# ProDoc_P1_2024-07-02.net
KiCad netlist of a schematic drawn in EasyEDA Pro
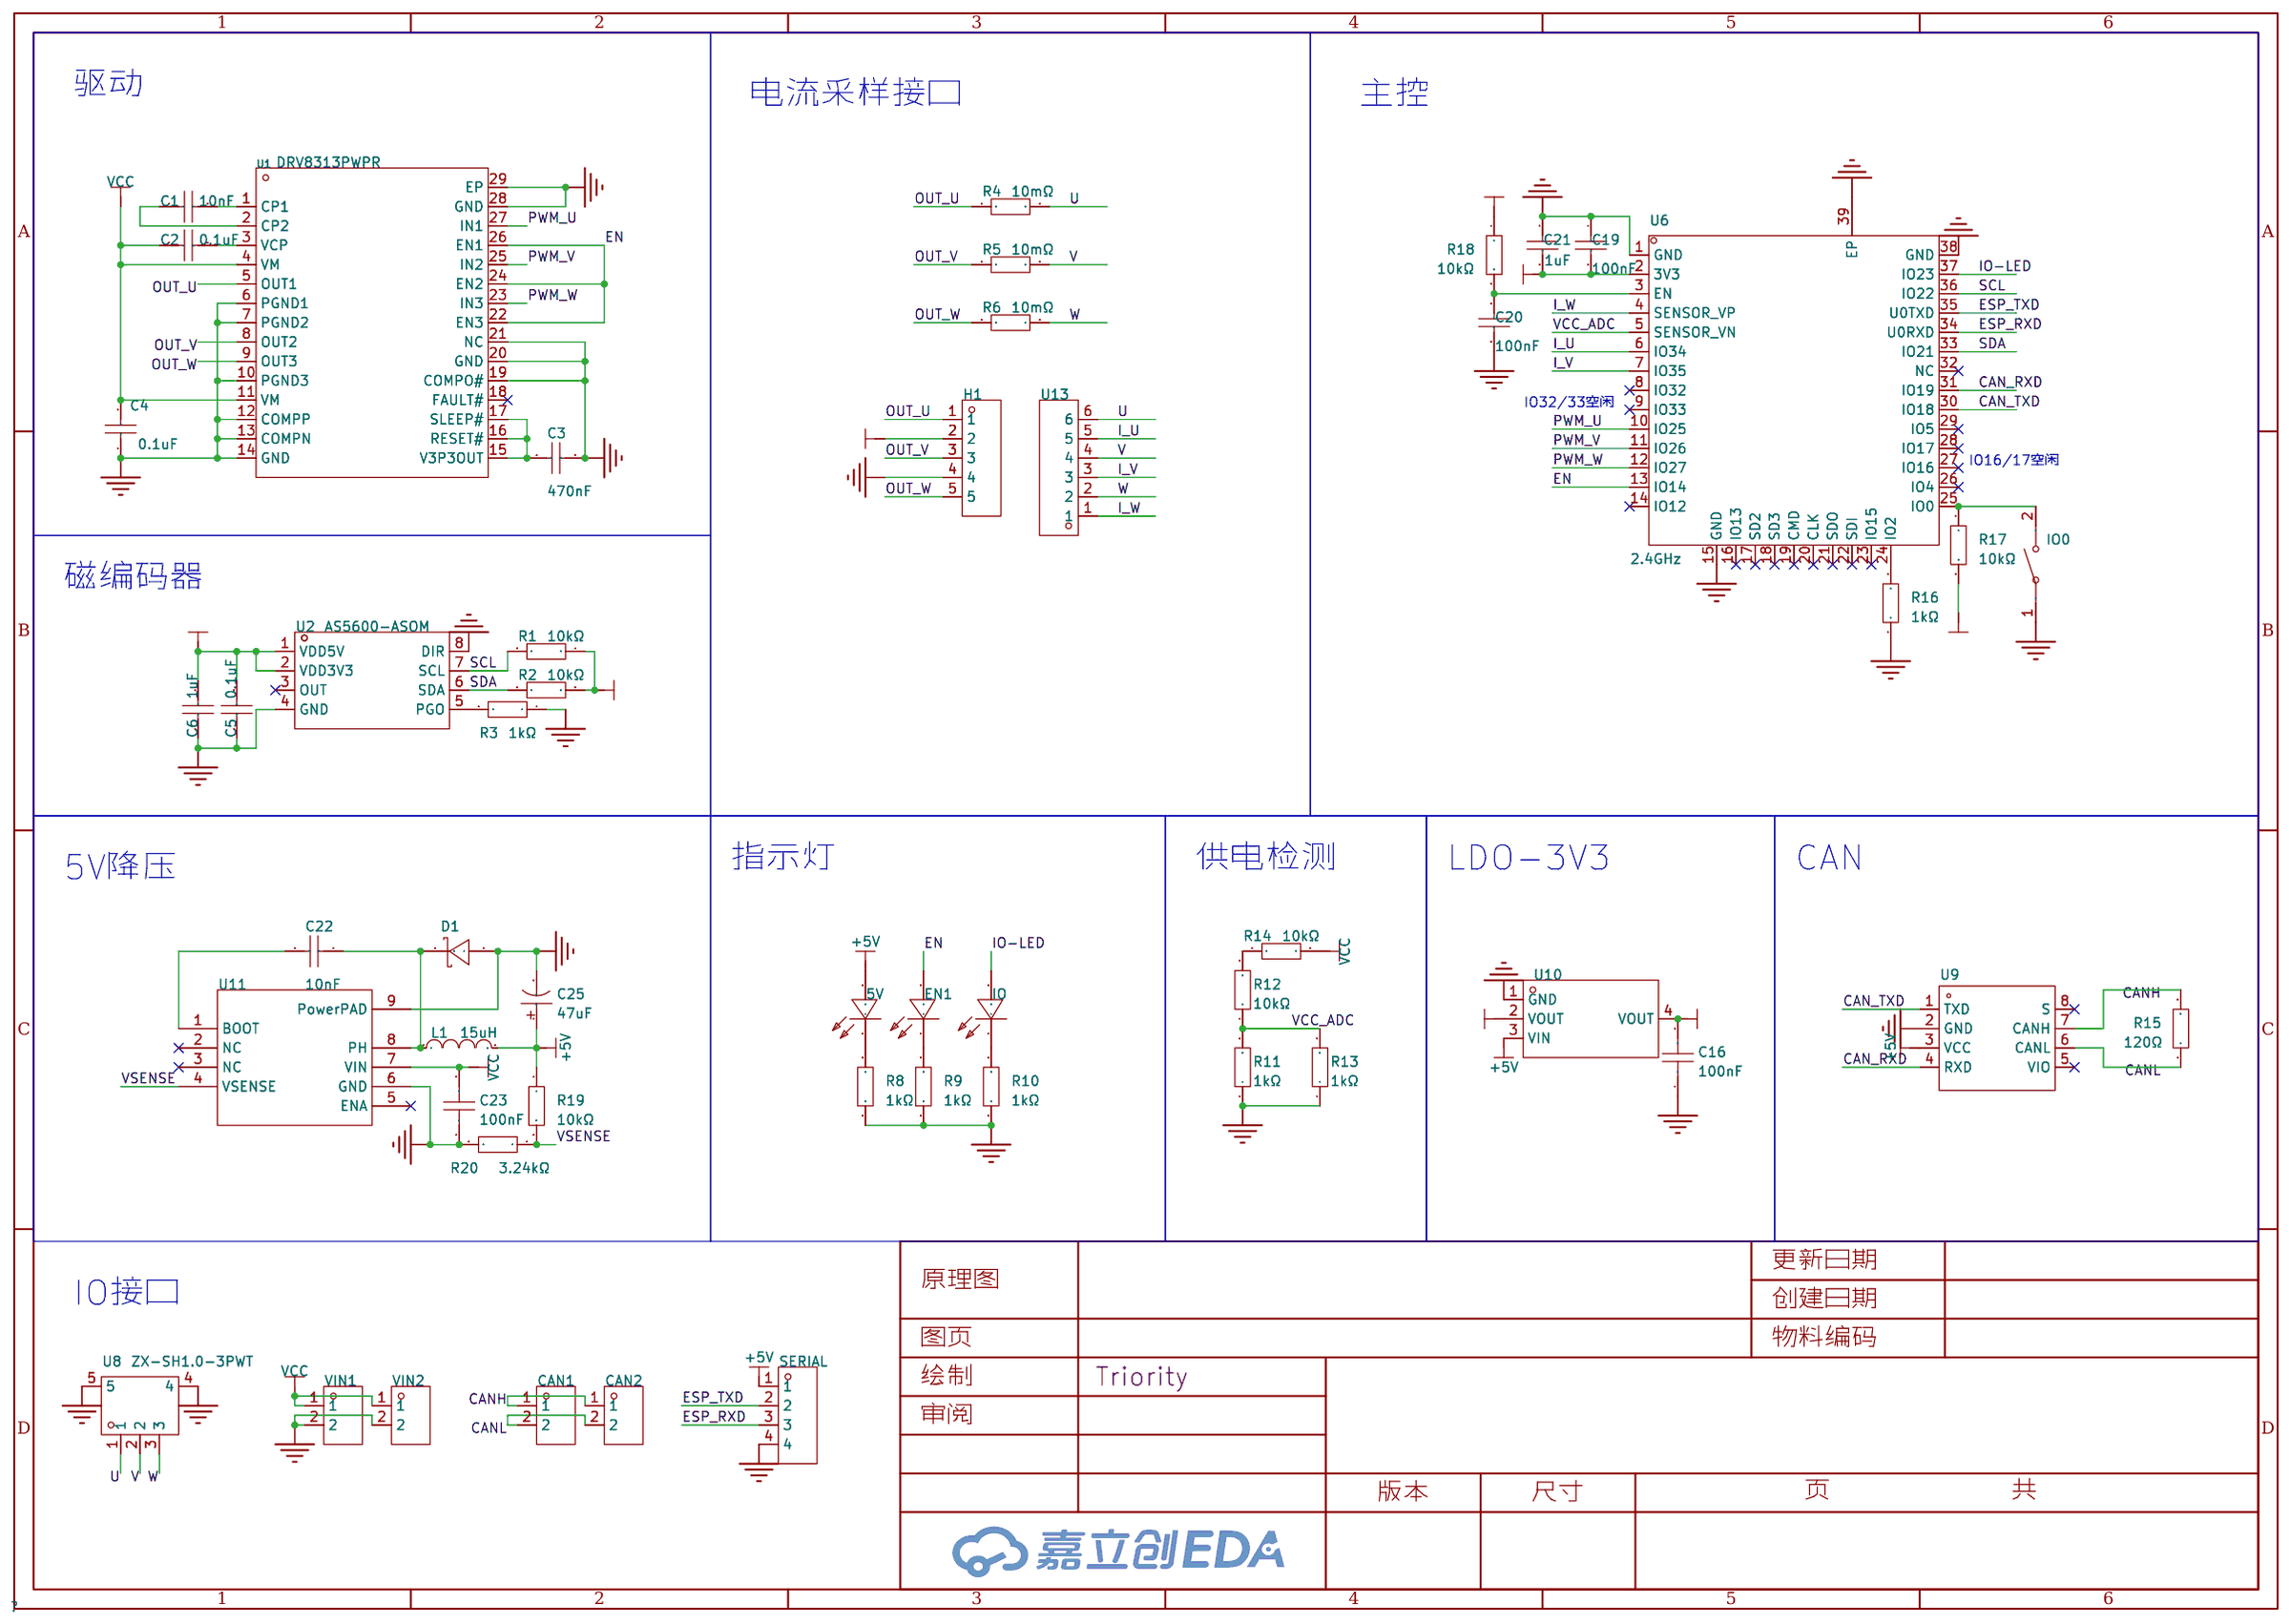
[diagram p0: schematic sheet]

(export (version "E")
  (design (tool "Eeschema 10.0.6"))
  (components
    (comp (ref "5V")
      (value "KT-0603R")
      (footprint "easyedapro:LED0603-RD")
      (description "发光颜色:红色;功率:-;正向电流:-;主波长:-;二极管配置:-;透镜颜色:-;色温:-;发光角度:-;载带方式:-;工作温度:-40°C~+85°C;")
      (fields (field (name "Manufacturer") "KENTO"))
      (libsource (lib "easyedapro") (part "KT-0603R"))
    )
    (comp (ref "C1")
      (value "10nF")
      (footprint "easyedapro:C0603")
      (description "容值:10nF;精度:±10%;额定电压:50V;材质(温度系数):X7R;")
      (fields
        (field (name "Manufacturer Part") "CC0603KRX7R9BB103")
        (field (name "Manufacturer") "YAGEO(国巨)")
      )
      (libsource (lib "easyedapro") (part "CC0603KRX7R9BB103"))
    )
    (comp (ref "C2")
      (value "0.1uF")
      (footprint "easyedapro:C0603")
      (description "容值:100nF;精度:±10%;额定电压:50V;材质(温度系数):X7R;")
      (fields (field (name "Manufacturer Part") "0603B104K500NT") (field (name "Manufacturer") "FH(风华)"))
      (libsource (lib "easyedapro") (part "0603B104K500NT"))
    )
    (comp (ref "C3")
      (value "470nF")
      (footprint "easyedapro:C0603")
      (description "容值:470nF;精度:±10%;额定电压:25V;材质(温度系数):X7R;")
      (fields
        (field (name "Manufacturer Part") "CL10B474KA8NNNC")
        (field (name "Manufacturer") "SAMSUNG(三星)")
      )
      (libsource (lib "easyedapro") (part "CL10B474KA8NNNC"))
    )
    (comp (ref "C4")
      (value "0.1uF")
      (footprint "easyedapro:C0603")
      (description "容值:100nF;精度:±10%;额定电压:50V;材质(温度系数):X7R;")
      (fields (field (name "Manufacturer Part") "0603B104K500NT") (field (name "Manufacturer") "FH(风华)"))
      (libsource (lib "easyedapro") (part "0603B104K500NT"))
    )
    (comp (ref "C5")
      (value "0.1uF")
      (footprint "easyedapro:C0603")
      (description "容值:100nF;精度:±10%;额定电压:50V;材质(温度系数):X7R;")
      (fields (field (name "Manufacturer Part") "0603B104K500NT") (field (name "Manufacturer") "FH(风华)"))
      (libsource (lib "easyedapro") (part "0603B104K500NT"))
    )
    (comp (ref "C6")
      (value "1uF")
      (footprint "easyedapro:C0603")
      (description "容值:1uF;精度:±10%;额定电压:50V;材质(温度系数):X5R;")
      (fields
        (field (name "Manufacturer Part") "CL10A105KB8NNNC")
        (field (name "Manufacturer") "SAMSUNG(三星)")
      )
      (libsource (lib "easyedapro") (part "CL10A105KB8NNNC"))
    )
    (comp (ref "C16")
      (value "100nF")
      (footprint "easyedapro:C0603")
      (description "容值:100nF;精度:±10%;额定电压:50V;材质(温度系数):X7R;")
      (fields
        (field (name "Manufacturer Part") "CC0603KRX7R9BB104")
        (field (name "Manufacturer") "YAGEO(国巨)")
      )
      (libsource (lib "easyedapro") (part "CC0603KRX7R9BB104"))
    )
    (comp (ref "C19")
      (value "100nF")
      (footprint "easyedapro:C0603")
      (description "容值:100nF;精度:±10%;额定电压:50V;材质(温度系数):X7R;")
      (fields (field (name "Manufacturer Part") "0603B104K500NT") (field (name "Manufacturer") "FH(风华)"))
      (libsource (lib "easyedapro") (part "0603B104K500NT"))
    )
    (comp (ref "C20")
      (value "100nF")
      (footprint "easyedapro:C0603")
      (description "容值:100nF;精度:±10%;额定电压:50V;材质(温度系数):X7R;")
      (fields (field (name "Manufacturer Part") "0603B104K500NT") (field (name "Manufacturer") "FH(风华)"))
      (libsource (lib "easyedapro") (part "0603B104K500NT"))
    )
    (comp (ref "C21")
      (value "1uF")
      (footprint "easyedapro:C0603")
      (description "容值:1uF;精度:±10%;额定电压:50V;材质(温度系数):X5R;")
      (fields
        (field (name "Manufacturer Part") "CL10A105KB8NNNC")
        (field (name "Manufacturer") "SAMSUNG(三星)")
      )
      (libsource (lib "easyedapro") (part "CL10A105KB8NNNC"))
    )
    (comp (ref "C22")
      (value "10nF")
      (footprint "easyedapro:C0603")
      (description "容值:10nF;精度:±10%;额定电压:50V;材质(温度系数):X7R;")
      (fields (field (name "Manufacturer Part") "0603B103K500NT") (field (name "Manufacturer") "FH(风华)"))
      (libsource (lib "easyedapro") (part "0603B103K500NT"))
    )
    (comp (ref "C23")
      (value "100nF")
      (footprint "easyedapro:C0603")
      (description "容值:100nF;精度:±10%;额定电压:50V;材质(温度系数):X7R;")
      (fields
        (field (name "Manufacturer Part") "CC0603KRX7R9BB104")
        (field (name "Manufacturer") "YAGEO(国巨)")
      )
      (libsource (lib "easyedapro") (part "CC0603KRX7R9BB104"))
    )
    (comp (ref "C25")
      (value "47uF")
      (footprint "easyedapro:CAP-SMD_BD4.0-L4.3-W4.3-LS5.3-FD")
      (description "容值:47uF;精度:±20%;额定电压:10V;纹波电流:31mA@120Hz;等效串联电阻:-;")
      (fields (field (name "Manufacturer Part") "RVT1A470M0405") (field (name "Manufacturer") "ROQANG(容强)"))
      (libsource (lib "easyedapro") (part "RVT1A470M0405"))
    )
    (comp (ref "CAN1")
      (value "ZX-XH2.54-2PWZ")
      (footprint "easyedapro:CONN-TH_2P-P2.50_ZX-XH2.54-2PWZ")
      (fields (field (name "Manufacturer") "Megastar(兆星)"))
      (libsource (lib "easyedapro") (part "ZX-XH2.54-2PWZ"))
    )
    (comp (ref "CAN2")
      (value "ZX-XH2.54-2PWZ")
      (footprint "easyedapro:CONN-TH_2P-P2.50_ZX-XH2.54-2PWZ")
      (fields (field (name "Manufacturer") "Megastar(兆星)"))
      (libsource (lib "easyedapro") (part "ZX-XH2.54-2PWZ"))
    )
    (comp (ref "D1")
      (value "B340A")
      (footprint "easyedapro:SMA_L4.3-W2.6-LS5.1-RD")
      (description "二极管配置:独立式;正向压降(Vf):550mV@3A;直流反向耐压(Vr):40V;整流电流:3A;")
      (fields (field (name "Manufacturer") "MDD(辰达半导体)"))
      (libsource (lib "easyedapro") (part "B340A"))
    )
    (comp (ref "EN1")
      (value "KT-0603R")
      (footprint "easyedapro:LED0603-RD")
      (description "发光颜色:红色;功率:-;正向电流:-;主波长:-;二极管配置:-;透镜颜色:-;色温:-;发光角度:-;载带方式:-;工作温度:-40°C~+85°C;")
      (fields (field (name "Manufacturer") "KENTO"))
      (libsource (lib "easyedapro") (part "KT-0603R"))
    )
    (comp (ref "H1")
      (value "PZ254V-11-05P")
      (footprint "easyedapro:HDR-TH_5P-P2.54-V-M")
      (fields (field (name "Manufacturer") "XFCN(兴飞)"))
      (libsource (lib "easyedapro") (part "PZ254V-11-05P"))
    )
    (comp (ref "IO")
      (value "KT-0603R")
      (footprint "easyedapro:LED0603-RD")
      (description "发光颜色:红色;功率:-;正向电流:-;主波长:-;二极管配置:-;透镜颜色:-;色温:-;发光角度:-;载带方式:-;工作温度:-40°C~+85°C;")
      (fields (field (name "Manufacturer") "KENTO"))
      (libsource (lib "easyedapro") (part "KT-0603R"))
    )
    (comp (ref "IO0")
      (value "K2-1107ST-A4DW-06")
      (footprint "easyedapro:KEY-SMD_L6.2-W3.6-LS8.0")
      (fields (field (name "Manufacturer") "韩国韩荣"))
      (libsource (lib "easyedapro") (part "K2-1107ST-A4SW-06"))
    )
    (comp (ref "L1")
      (value "15uH")
      (footprint "easyedapro:IND-SMD_L7.3-W6.8")
      (description "电感值:15uH;精度:±20%;额定电流:3A;饱和电流(Isat):4A;类型:-;")
      (fields
        (field (name "Manufacturer Part") "MWSA0603S-150MT")
        (field (name "Manufacturer") "Sunlord(顺络)")
      )
      (libsource (lib "easyedapro") (part "MWSA0603S-150MT"))
    )
    (comp (ref "R1")
      (value "10kΩ")
      (footprint "easyedapro:R0603")
      (description "电阻类型:厚膜电阻;阻值:10kΩ;精度:±1%;功率:100mW;最大工作电压:75V;温度系数:±100ppm/°C;")
      (fields (field (name "Manufacturer Part") "RC0603FR-0710KL") (field (name "Manufacturer") "YAGEO(国巨)"))
      (libsource (lib "easyedapro") (part "RC0603FR-0710KL"))
    )
    (comp (ref "R2")
      (value "10kΩ")
      (footprint "easyedapro:R0603")
      (description "电阻类型:厚膜电阻;阻值:10kΩ;精度:±1%;功率:100mW;最大工作电压:75V;温度系数:±100ppm/°C;")
      (fields (field (name "Manufacturer Part") "RC0603FR-0710KL") (field (name "Manufacturer") "YAGEO(国巨)"))
      (libsource (lib "easyedapro") (part "RC0603FR-0710KL"))
    )
    (comp (ref "R3")
      (value "1kΩ")
      (footprint "easyedapro:R0603")
      (description "电阻类型:厚膜电阻;阻值:1kΩ;精度:±1%;功率:100mW;最大工作电压:75V;温度系数:±100ppm/°C;")
      (fields (field (name "Manufacturer Part") "RC0603FR-071KL") (field (name "Manufacturer") "YAGEO(国巨)"))
      (libsource (lib "easyedapro") (part "RC0603FR-071KL"))
    )
    (comp (ref "R4")
      (value "10mΩ")
      (footprint "easyedapro:R1206")
      (description "阻值:10mΩ;精度:±1%;功率:1W;温度系数:±100ppm/°C;")
      (fields (field (name "Manufacturer Part") "RLM12FTCMR010") (field (name "Manufacturer") "大毅科技"))
      (libsource (lib "easyedapro") (part "RLM12FTCMR010"))
    )
    (comp (ref "R5")
      (value "10mΩ")
      (footprint "easyedapro:R1206")
      (description "阻值:10mΩ;精度:±1%;功率:1W;温度系数:±100ppm/°C;")
      (fields (field (name "Manufacturer Part") "RLM12FTCMR010") (field (name "Manufacturer") "大毅科技"))
      (libsource (lib "easyedapro") (part "RLM12FTCMR010"))
    )
    (comp (ref "R6")
      (value "10mΩ")
      (footprint "easyedapro:R1206")
      (description "阻值:10mΩ;精度:±1%;功率:1W;温度系数:±100ppm/°C;")
      (fields (field (name "Manufacturer Part") "RLM12FTCMR010") (field (name "Manufacturer") "大毅科技"))
      (libsource (lib "easyedapro") (part "RLM12FTCMR010"))
    )
    (comp (ref "R8")
      (value "1kΩ")
      (footprint "easyedapro:R0603")
      (description "电阻类型:厚膜电阻;阻值:1kΩ;精度:±1%;功率:100mW;最大工作电压:75V;温度系数:±100ppm/°C;")
      (fields
        (field (name "Manufacturer Part") "0603WAF1001T5E")
        (field (name "Manufacturer") "UNI-ROYAL(厚声)")
      )
      (libsource (lib "easyedapro") (part "0603WAF1001T5E"))
    )
    (comp (ref "R9")
      (value "1kΩ")
      (footprint "easyedapro:R0603")
      (description "电阻类型:厚膜电阻;阻值:1kΩ;精度:±1%;功率:100mW;最大工作电压:75V;温度系数:±100ppm/°C;")
      (fields
        (field (name "Manufacturer Part") "0603WAF1001T5E")
        (field (name "Manufacturer") "UNI-ROYAL(厚声)")
      )
      (libsource (lib "easyedapro") (part "0603WAF1001T5E"))
    )
    (comp (ref "R10")
      (value "1kΩ")
      (footprint "easyedapro:R0603")
      (description "电阻类型:厚膜电阻;阻值:1kΩ;精度:±1%;功率:100mW;最大工作电压:75V;温度系数:±100ppm/°C;")
      (fields
        (field (name "Manufacturer Part") "0603WAF1001T5E")
        (field (name "Manufacturer") "UNI-ROYAL(厚声)")
      )
      (libsource (lib "easyedapro") (part "0603WAF1001T5E"))
    )
    (comp (ref "R11")
      (value "1kΩ")
      (footprint "easyedapro:R0603")
      (description "电阻类型:厚膜电阻;阻值:1kΩ;精度:±1%;功率:100mW;最大工作电压:75V;温度系数:±100ppm/°C;")
      (fields
        (field (name "Manufacturer Part") "0603WAF1001T5E")
        (field (name "Manufacturer") "UNI-ROYAL(厚声)")
      )
      (libsource (lib "easyedapro") (part "0603WAF1001T5E"))
    )
    (comp (ref "R12")
      (value "10kΩ")
      (footprint "easyedapro:R0603")
      (description "电阻类型:厚膜电阻;阻值:10kΩ;精度:±1%;功率:100mW;最大工作电压:75V;温度系数:±100ppm/°C;")
      (fields (field (name "Manufacturer Part") "RC0603FR-0710KL") (field (name "Manufacturer") "YAGEO(国巨)"))
      (libsource (lib "easyedapro") (part "RC0603FR-0710KL"))
    )
    (comp (ref "R13")
      (value "1kΩ")
      (footprint "easyedapro:R0603")
      (description "电阻类型:厚膜电阻;阻值:1kΩ;精度:±1%;功率:100mW;最大工作电压:75V;温度系数:±100ppm/°C;")
      (fields
        (field (name "Manufacturer Part") "0603WAF1001T5E")
        (field (name "Manufacturer") "UNI-ROYAL(厚声)")
      )
      (libsource (lib "easyedapro") (part "0603WAF1001T5E"))
    )
    (comp (ref "R14")
      (value "10kΩ")
      (footprint "easyedapro:R0603")
      (description "电阻类型:厚膜电阻;阻值:10kΩ;精度:±1%;功率:100mW;最大工作电压:75V;温度系数:±100ppm/°C;")
      (fields (field (name "Manufacturer Part") "RC0603FR-0710KL") (field (name "Manufacturer") "YAGEO(国巨)"))
      (libsource (lib "easyedapro") (part "RC0603FR-0710KL"))
    )
    (comp (ref "R15")
      (value "120Ω")
      (footprint "easyedapro:R0603")
      (description "电阻类型:厚膜电阻;阻值:120Ω;精度:±1%;功率:100mW;最大工作电压:75V;温度系数:±100ppm/°C;")
      (fields
        (field (name "Manufacturer Part") "0603WAF1200T5E")
        (field (name "Manufacturer") "UNI-ROYAL(厚声)")
      )
      (libsource (lib "easyedapro") (part "0603WAF1200T5E"))
    )
    (comp (ref "R16")
      (value "1kΩ")
      (footprint "easyedapro:R0603")
      (description "电阻类型:厚膜电阻;阻值:1kΩ;精度:±1%;功率:100mW;最大工作电压:75V;温度系数:±100ppm/°C;")
      (fields
        (field (name "Manufacturer Part") "0603WAF1001T5E")
        (field (name "Manufacturer") "UNI-ROYAL(厚声)")
      )
      (libsource (lib "easyedapro") (part "0603WAF1001T5E"))
    )
    (comp (ref "R17")
      (value "10kΩ")
      (footprint "easyedapro:R0603")
      (description "电阻类型:厚膜电阻;阻值:10kΩ;精度:±1%;功率:100mW;最大工作电压:75V;温度系数:±100ppm/°C;")
      (fields (field (name "Manufacturer Part") "RC0603FR-0710KL") (field (name "Manufacturer") "YAGEO(国巨)"))
      (libsource (lib "easyedapro") (part "RC0603FR-0710KL"))
    )
    (comp (ref "R18")
      (value "10kΩ")
      (footprint "easyedapro:R0603")
      (description "电阻类型:厚膜电阻;阻值:10kΩ;精度:±1%;功率:100mW;最大工作电压:75V;温度系数:±100ppm/°C;")
      (fields (field (name "Manufacturer Part") "RC0603FR-0710KL") (field (name "Manufacturer") "YAGEO(国巨)"))
      (libsource (lib "easyedapro") (part "RC0603FR-0710KL"))
    )
    (comp (ref "R19")
      (value "10kΩ")
      (footprint "easyedapro:R0603")
      (description "电阻类型:厚膜电阻;阻值:10kΩ;精度:±1%;功率:100mW;最大工作电压:75V;温度系数:±100ppm/°C;")
      (fields (field (name "Manufacturer Part") "RC0603FR-0710KL") (field (name "Manufacturer") "YAGEO(国巨)"))
      (libsource (lib "easyedapro") (part "RC0603FR-0710KL"))
    )
    (comp (ref "R20")
      (value "3.24kΩ")
      (footprint "easyedapro:R0603")
      (description "电阻类型:厚膜电阻;阻值:3.24kΩ;精度:±1%;功率:100mW;最大工作电压:75V;温度系数:±100ppm/°C;")
      (fields
        (field (name "Manufacturer Part") "0603WAF3241T5E")
        (field (name "Manufacturer") "UNI-ROYAL(厚声)")
      )
      (libsource (lib "easyedapro") (part "0603WAF3241T5E"))
    )
    (comp (ref "SERIAL")
      (value "WAFER-XH2.54-4PWZ")
      (footprint "easyedapro:CONN-TH_4P-P2.50_WAFER-XH2.54-4PWZ")
      (description "插针结构:1x4P;间距:2.54mm;安装方式:弯插;总PIN数:4P;排数:1;每排PIN数:4;额定电流:2A;工作温度范围:-25°C~+85°C;")
      (fields (field (name "Manufacturer") "XUNPU(讯普)"))
      (libsource (lib "easyedapro") (part "WAFER-XH2.54-4PWZ"))
    )
    (comp (ref "U1")
      (value "DRV8313PWPR")
      (footprint "easyedapro:HTSSOP-28_L9.8-W4.5-P0.65-LS6.6-BL-EP")
      (description "驱动电机类型:无刷直流BLDC;电源电压:8V~60V;输出电流:-;接口:并行;")
      (fields (field (name "Manufacturer") "TI(德州仪器)"))
      (libsource (lib "easyedapro") (part "DRV8313PWPR"))
    )
    (comp (ref "U2")
      (value "AS5600-ASOM")
      (footprint "easyedapro:SOIC-8_L5.0-W4.0-P1.27-LS6.0-BL")
      (description "旋转角度范围:0°~360°;")
      (fields (field (name "Manufacturer") "ams(艾迈斯半导体)"))
      (libsource (lib "easyedapro") (part "AS5600-ASOM"))
    )
    (comp (ref "U6")
      (value "2.4GHz")
      (footprint "easyedapro:WIRELM-SMD_ESP32-S")
      (description "核心处理器:ESP32芯片;频率:2.4GHz;天线形式:IPEX接口;发射功率:17dBm;接收灵敏度:-90dBm;")
      (fields (field (name "Manufacturer Part") "ESP32-S") (field (name "Manufacturer") "Ai-Thinker(安信可)"))
      (libsource (lib "easyedapro") (part "ESP32-S"))
    )
    (comp (ref "U8")
      (value "ZX-SH1.0-3PWT")
      (footprint "easyedapro:CONN-SMD_3P-P1.00_MEGASTAR_ZX-SH1.0-3PWT")
      (fields (field (name "Manufacturer") "Megastar(兆星)"))
      (libsource (lib "easyedapro") (part "ZX-SH1.0-3PWT"))
    )
    (comp (ref "U9")
      (value "TJA1051T/3/1J")
      (footprint "easyedapro:SOIC-8_L4.9-W3.9-P1.27-LS6.0-BL")
      (description "类型:收发器;数据速率:5Mbps;")
      (fields (field (name "Manufacturer") "NXP(恩智浦)"))
      (libsource (lib "easyedapro") (part "TJA1051T/3/1J"))
    )
    (comp (ref "U10")
      (value "AMS1117-3.3")
      (footprint "easyedapro:SOT-223-3_L6.5-W3.4-P2.30-LS7.0-BR")
      (description "输出类型:固定;最大输入电压:-;输出电压:3.3V;最大输出电流:1A;电源纹波抑制比(PSRR):72dB@(120Hz);输出极性:正极;")
      (fields (field (name "Manufacturer") "AMS"))
      (libsource (lib "easyedapro") (part "AMS1117-3.3"))
    )
    (comp (ref "U11")
      (value "TPS5430DDAR")
      (footprint "easyedapro:ESOP-8_L4.9-W3.9-P1.27-LS6.0-TL-EP")
      (description "功能类型:降压型;输出类型:可调;输入电压:5.5V~36V;输出电压:1.221V~32.04V;输出电流(最大值):3A;")
      (fields (field (name "Manufacturer") "TI(德州仪器)"))
      (libsource (lib "easyedapro") (part "TPS5430DDAR"))
    )
    (comp (ref "U13")
      (value "PZ254V-11-06-0950")
      (footprint "easyedapro:HDR-TH_6P-P2.54-V-M-1")
      (fields (field (name "Manufacturer") "XFCN(兴飞)"))
      (libsource (lib "easyedapro") (part "PZ254V-11-06-0950"))
    )
    (comp (ref "VIN1")
      (value "ZX-XH2.54-2PWZ")
      (footprint "easyedapro:CONN-TH_2P-P2.50_ZX-XH2.54-2PWZ")
      (fields (field (name "Manufacturer") "Megastar(兆星)"))
      (libsource (lib "easyedapro") (part "ZX-XH2.54-2PWZ"))
    )
    (comp (ref "VIN2")
      (value "ZX-XH2.54-2PWZ")
      (footprint "easyedapro:CONN-TH_2P-P2.50_ZX-XH2.54-2PWZ")
      (fields (field (name "Manufacturer") "Megastar(兆星)"))
      (libsource (lib "easyedapro") (part "ZX-XH2.54-2PWZ"))
    )
  )
  (nets
    (net (code "1") (name "+5V") (class "Default")
      (node (ref "5V") (pin "2") (pinfunction "A_2") (pintype "input"))
      (node (ref "C25") (pin "1") (pinfunction "1_1") (pintype "input"))
      (node (ref "L1") (pin "2") (pinfunction "2_2") (pintype "unspecified"))
      (node (ref "R19") (pin "1") (pinfunction "1_1") (pintype "input"))
      (node (ref "SERIAL") (pin "1") (pinfunction "1_1") (pintype "unspecified"))
      (node (ref "U10") (pin "3") (pinfunction "VIN_3") (pintype "unspecified"))
      (node (ref "U9") (pin "3") (pinfunction "VCC_3") (pintype "input"))
    )
    (net (code "2") (name "/CANH") (class "Default")
      (node (ref "CAN1") (pin "1") (pinfunction "1_1") (pintype "unspecified"))
      (node (ref "CAN2") (pin "1") (pinfunction "1_1") (pintype "unspecified"))
      (node (ref "R15") (pin "2") (pinfunction "2_2") (pintype "input"))
      (node (ref "U9") (pin "7") (pinfunction "CANH_7") (pintype "input"))
    )
    (net (code "3") (name "/CANL") (class "Default")
      (node (ref "CAN1") (pin "2") (pinfunction "2_2") (pintype "unspecified"))
      (node (ref "CAN2") (pin "2") (pinfunction "2_2") (pintype "unspecified"))
      (node (ref "R15") (pin "1") (pinfunction "1_1") (pintype "input"))
      (node (ref "U9") (pin "6") (pinfunction "CANL_6") (pintype "input"))
    )
    (net (code "4") (name "/CAN_RXD") (class "Default")
      (node (ref "U6") (pin "31") (pinfunction "IO19_31") (pintype "input"))
      (node (ref "U9") (pin "4") (pinfunction "RXD_4") (pintype "input"))
    )
    (net (code "5") (name "/CAN_TXD") (class "Default")
      (node (ref "U6") (pin "30") (pinfunction "IO18_30") (pintype "input"))
      (node (ref "U9") (pin "1") (pinfunction "TXD_1") (pintype "input"))
    )
    (net (code "6") (name "/EN") (class "Default")
      (node (ref "EN1") (pin "2") (pinfunction "A_2") (pintype "input"))
      (node (ref "U1") (pin "22") (pinfunction "EN3_22") (pintype "input"))
      (node (ref "U1") (pin "24") (pinfunction "EN2_24") (pintype "input"))
      (node (ref "U1") (pin "26") (pinfunction "EN1_26") (pintype "input"))
      (node (ref "U6") (pin "13") (pinfunction "IO14_13") (pintype "input"))
    )
    (net (code "7") (name "/ESP_RXD") (class "Default")
      (node (ref "SERIAL") (pin "3") (pinfunction "3_3") (pintype "unspecified"))
      (node (ref "U6") (pin "34") (pinfunction "U0RXD_34") (pintype "input"))
    )
    (net (code "8") (name "/ESP_TXD") (class "Default")
      (node (ref "SERIAL") (pin "2") (pinfunction "2_2") (pintype "unspecified"))
      (node (ref "U6") (pin "35") (pinfunction "U0TXD_35") (pintype "input"))
    )
    (net (code "9") (name "/IO-LED") (class "Default")
      (node (ref "IO") (pin "2") (pinfunction "A_2") (pintype "input"))
      (node (ref "U6") (pin "37") (pinfunction "IO23_37") (pintype "input"))
    )
    (net (code "10") (name "/I_U") (class "Default")
      (node (ref "U13") (pin "5") (pinfunction "5_5") (pintype "input"))
      (node (ref "U6") (pin "6") (pinfunction "IO34_6") (pintype "input"))
    )
    (net (code "11") (name "/I_V") (class "Default")
      (node (ref "U13") (pin "3") (pinfunction "3_3") (pintype "input"))
      (node (ref "U6") (pin "7") (pinfunction "IO35_7") (pintype "input"))
    )
    (net (code "12") (name "/I_W") (class "Default")
      (node (ref "U13") (pin "1") (pinfunction "1_1") (pintype "input"))
      (node (ref "U6") (pin "4") (pinfunction "SENSOR_VP_4") (pintype "input"))
    )
    (net (code "13") (name "/OUT_U") (class "Default")
      (node (ref "H1") (pin "1") (pinfunction "1_1") (pintype "unspecified"))
      (node (ref "R4") (pin "1") (pinfunction "1_1") (pintype "input"))
      (node (ref "U1") (pin "5") (pinfunction "OUT1_5") (pintype "input"))
    )
    (net (code "14") (name "/OUT_V") (class "Default")
      (node (ref "H1") (pin "3") (pinfunction "3_3") (pintype "unspecified"))
      (node (ref "R5") (pin "1") (pinfunction "1_1") (pintype "input"))
      (node (ref "U1") (pin "8") (pinfunction "OUT2_8") (pintype "input"))
    )
    (net (code "15") (name "/OUT_W") (class "Default")
      (node (ref "H1") (pin "5") (pinfunction "5_5") (pintype "unspecified"))
      (node (ref "R6") (pin "1") (pinfunction "1_1") (pintype "input"))
      (node (ref "U1") (pin "9") (pinfunction "OUT3_9") (pintype "input"))
    )
    (net (code "16") (name "/PWM_U") (class "Default")
      (node (ref "U1") (pin "27") (pinfunction "IN1_27") (pintype "input"))
      (node (ref "U6") (pin "10") (pinfunction "IO25_10") (pintype "input"))
    )
    (net (code "17") (name "/PWM_V") (class "Default")
      (node (ref "U1") (pin "25") (pinfunction "IN2_25") (pintype "input"))
      (node (ref "U6") (pin "11") (pinfunction "IO26_11") (pintype "input"))
    )
    (net (code "18") (name "/PWM_W") (class "Default")
      (node (ref "U1") (pin "23") (pinfunction "IN3_23") (pintype "input"))
      (node (ref "U6") (pin "12") (pinfunction "IO27_12") (pintype "input"))
    )
    (net (code "19") (name "/SCL") (class "Default")
      (node (ref "R1") (pin "2") (pinfunction "2_2") (pintype "input"))
      (node (ref "U2") (pin "7") (pinfunction "SCL_7") (pintype "input"))
      (node (ref "U6") (pin "36") (pinfunction "IO22_36") (pintype "input"))
    )
    (net (code "20") (name "/SDA") (class "Default")
      (node (ref "R2") (pin "2") (pinfunction "2_2") (pintype "input"))
      (node (ref "U2") (pin "6") (pinfunction "SDA_6") (pintype "input"))
      (node (ref "U6") (pin "33") (pinfunction "IO21_33") (pintype "input"))
    )
    (net (code "21") (name "/U") (class "Default")
      (node (ref "R4") (pin "2") (pinfunction "2_2") (pintype "input"))
      (node (ref "U13") (pin "6") (pinfunction "6_6") (pintype "input"))
      (node (ref "U8") (pin "1") (pinfunction "1_1") (pintype "unspecified"))
    )
    (net (code "22") (name "/V") (class "Default")
      (node (ref "R5") (pin "2") (pinfunction "2_2") (pintype "input"))
      (node (ref "U13") (pin "4") (pinfunction "4_4") (pintype "input"))
      (node (ref "U8") (pin "2") (pinfunction "2_2") (pintype "unspecified"))
    )
    (net (code "23") (name "/VCC_ADC") (class "Default")
      (node (ref "R11") (pin "2") (pinfunction "2_2") (pintype "input"))
      (node (ref "R12") (pin "1") (pinfunction "1_1") (pintype "input"))
      (node (ref "R13") (pin "2") (pinfunction "2_2") (pintype "input"))
      (node (ref "U6") (pin "5") (pinfunction "SENSOR_VN_5") (pintype "input"))
    )
    (net (code "24") (name "/VSENSE") (class "Default")
      (node (ref "R19") (pin "2") (pinfunction "2_2") (pintype "input"))
      (node (ref "R20") (pin "1") (pinfunction "1_1") (pintype "input"))
      (node (ref "U11") (pin "4") (pinfunction "VSENSE_4") (pintype "unspecified"))
    )
    (net (code "25") (name "/W") (class "Default")
      (node (ref "R6") (pin "2") (pinfunction "2_2") (pintype "input"))
      (node (ref "U13") (pin "2") (pinfunction "2_2") (pintype "input"))
      (node (ref "U8") (pin "3") (pinfunction "3_3") (pintype "unspecified"))
    )
    (net (code "26") (name "3V3") (class "Default")
      (node (ref "C16") (pin "2") (pinfunction "2_2") (pintype "unspecified"))
      (node (ref "C19") (pin "2") (pinfunction "2_2") (pintype "input"))
      (node (ref "C21") (pin "1") (pinfunction "1_1") (pintype "input"))
      (node (ref "C5") (pin "2") (pinfunction "2_2") (pintype "input"))
      (node (ref "C6") (pin "2") (pinfunction "2_2") (pintype "input"))
      (node (ref "H1") (pin "2") (pinfunction "2_2") (pintype "unspecified"))
      (node (ref "R1") (pin "1") (pinfunction "1_1") (pintype "input"))
      (node (ref "R17") (pin "2") (pinfunction "2_2") (pintype "input"))
      (node (ref "R18") (pin "1") (pinfunction "1_1") (pintype "input"))
      (node (ref "R2") (pin "1") (pinfunction "1_1") (pintype "input"))
      (node (ref "U10") (pin "2") (pinfunction "VOUT_2") (pintype "unspecified"))
      (node (ref "U10") (pin "4") (pinfunction "VOUT_4") (pintype "unspecified"))
      (node (ref "U2") (pin "1") (pinfunction "VDD5V_1") (pintype "input"))
      (node (ref "U2") (pin "2") (pinfunction "VDD3V3_2") (pintype "input"))
      (node (ref "U6") (pin "2") (pinfunction "3V3_2") (pintype "input"))
    )
    (net (code "27") (name "GND") (class "Default")
      (node (ref "C16") (pin "1") (pinfunction "1_1") (pintype "unspecified"))
      (node (ref "C19") (pin "1") (pinfunction "1_1") (pintype "input"))
      (node (ref "C20") (pin "2") (pinfunction "2_2") (pintype "input"))
      (node (ref "C21") (pin "2") (pinfunction "2_2") (pintype "input"))
      (node (ref "C23") (pin "1") (pinfunction "1_1") (pintype "unspecified"))
      (node (ref "C25") (pin "2") (pinfunction "2_2") (pintype "input"))
      (node (ref "C3") (pin "1") (pinfunction "1_1") (pintype "input"))
      (node (ref "C4") (pin "1") (pinfunction "1_1") (pintype "input"))
      (node (ref "C5") (pin "1") (pinfunction "1_1") (pintype "input"))
      (node (ref "C6") (pin "1") (pinfunction "1_1") (pintype "input"))
      (node (ref "D1") (pin "2") (pinfunction "A_2") (pintype "unspecified"))
      (node (ref "H1") (pin "4") (pinfunction "4_4") (pintype "unspecified"))
      (node (ref "IO0") (pin "1") (pinfunction "1_1") (pintype "input"))
      (node (ref "R10") (pin "1") (pinfunction "1_1") (pintype "input"))
      (node (ref "R11") (pin "1") (pinfunction "1_1") (pintype "input"))
      (node (ref "R13") (pin "1") (pinfunction "1_1") (pintype "input"))
      (node (ref "R16") (pin "1") (pinfunction "1_1") (pintype "input"))
      (node (ref "R20") (pin "2") (pinfunction "2_2") (pintype "input"))
      (node (ref "R3") (pin "1") (pinfunction "1_1") (pintype "input"))
      (node (ref "R8") (pin "1") (pinfunction "1_1") (pintype "input"))
      (node (ref "R9") (pin "1") (pinfunction "1_1") (pintype "input"))
      (node (ref "SERIAL") (pin "4") (pinfunction "4_4") (pintype "unspecified"))
      (node (ref "U1") (pin "10") (pinfunction "PGND3_10") (pintype "input"))
      (node (ref "U1") (pin "12") (pinfunction "COMPP_12") (pintype "input"))
      (node (ref "U1") (pin "13") (pinfunction "COMPN_13") (pintype "input"))
      (node (ref "U1") (pin "14") (pinfunction "GND_14") (pintype "input"))
      (node (ref "U1") (pin "19") (pinfunction "COMPO#_19") (pintype "input"))
      (node (ref "U1") (pin "20") (pinfunction "GND_20") (pintype "input"))
      (node (ref "U1") (pin "21") (pinfunction "NC_21") (pintype "input"))
      (node (ref "U1") (pin "28") (pinfunction "GND_28") (pintype "input"))
      (node (ref "U1") (pin "29") (pinfunction "EP_29") (pintype "input"))
      (node (ref "U1") (pin "6") (pinfunction "PGND1_6") (pintype "input"))
      (node (ref "U1") (pin "7") (pinfunction "PGND2_7") (pintype "input"))
      (node (ref "U10") (pin "1") (pinfunction "GND_1") (pintype "unspecified"))
      (node (ref "U11") (pin "6") (pinfunction "GND_6") (pintype "unspecified"))
      (node (ref "U11") (pin "9") (pinfunction "PowerPAD_9") (pintype "unspecified"))
      (node (ref "U2") (pin "4") (pinfunction "GND_4") (pintype "input"))
      (node (ref "U2") (pin "8") (pinfunction "DIR_8") (pintype "input"))
      (node (ref "U6") (pin "1") (pinfunction "GND_1") (pintype "input"))
      (node (ref "U6") (pin "15") (pinfunction "GND_15") (pintype "input"))
      (node (ref "U6") (pin "38") (pinfunction "GND_38") (pintype "input"))
      (node (ref "U6") (pin "39") (pinfunction "EP_39") (pintype "input"))
      (node (ref "U8") (pin "4") (pinfunction "4_4") (pintype "unspecified"))
      (node (ref "U8") (pin "5") (pinfunction "5_5") (pintype "unspecified"))
      (node (ref "U9") (pin "2") (pinfunction "GND_2") (pintype "input"))
      (node (ref "VIN1") (pin "2") (pinfunction "2_2") (pintype "unspecified"))
      (node (ref "VIN2") (pin "2") (pinfunction "2_2") (pintype "unspecified"))
    )
    (net (code "28") (name "Net-(5V-K)") (class "Default")
      (node (ref "5V") (pin "1") (pinfunction "K_1") (pintype "input"))
      (node (ref "R8") (pin "2") (pinfunction "2_2") (pintype "input"))
    )
    (net (code "29") (name "Net-(D1-K)") (class "Default")
      (node (ref "C22") (pin "1") (pinfunction "1_1") (pintype "input"))
      (node (ref "D1") (pin "1") (pinfunction "K_1") (pintype "unspecified"))
      (node (ref "L1") (pin "1") (pinfunction "1_1") (pintype "unspecified"))
      (node (ref "U11") (pin "8") (pinfunction "PH_8") (pintype "unspecified"))
    )
    (net (code "30") (name "Net-(EN1-K)") (class "Default")
      (node (ref "EN1") (pin "1") (pinfunction "K_1") (pintype "input"))
      (node (ref "R9") (pin "2") (pinfunction "2_2") (pintype "input"))
    )
    (net (code "31") (name "Net-(IO-K)") (class "Default")
      (node (ref "IO") (pin "1") (pinfunction "K_1") (pintype "input"))
      (node (ref "R10") (pin "2") (pinfunction "2_2") (pintype "input"))
    )
    (net (code "32") (name "Net-(R12-Pad2)") (class "Default")
      (node (ref "R12") (pin "2") (pinfunction "2_2") (pintype "input"))
      (node (ref "R14") (pin "2") (pinfunction "2_2") (pintype "input"))
    )
    (net (code "33") (name "Net-(U1-CP1)") (class "Default")
      (node (ref "C1") (pin "2") (pinfunction "2_2") (pintype "input"))
      (node (ref "U1") (pin "1") (pinfunction "CP1_1") (pintype "input"))
    )
    (net (code "34") (name "Net-(U1-CP2)") (class "Default")
      (node (ref "C1") (pin "1") (pinfunction "1_1") (pintype "input"))
      (node (ref "U1") (pin "2") (pinfunction "CP2_2") (pintype "input"))
    )
    (net (code "35") (name "Net-(U1-RESET#)") (class "Default")
      (node (ref "C3") (pin "2") (pinfunction "2_2") (pintype "input"))
      (node (ref "U1") (pin "15") (pinfunction "V3P3OUT_15") (pintype "input"))
      (node (ref "U1") (pin "16") (pinfunction "RESET#_16") (pintype "input"))
      (node (ref "U1") (pin "17") (pinfunction "SLEEP#_17") (pintype "input"))
    )
    (net (code "36") (name "Net-(U1-VCP)") (class "Default")
      (node (ref "C2") (pin "2") (pinfunction "2_2") (pintype "input"))
      (node (ref "U1") (pin "3") (pinfunction "VCP_3") (pintype "input"))
    )
    (net (code "37") (name "Net-(U2-PGO)") (class "Default")
      (node (ref "R3") (pin "2") (pinfunction "2_2") (pintype "input"))
      (node (ref "U2") (pin "5") (pinfunction "PGO_5") (pintype "input"))
    )
    (net (code "38") (name "Net-(U6-EN)") (class "Default")
      (node (ref "C20") (pin "1") (pinfunction "1_1") (pintype "input"))
      (node (ref "R18") (pin "2") (pinfunction "2_2") (pintype "input"))
      (node (ref "U6") (pin "3") (pinfunction "EN_3") (pintype "input"))
    )
    (net (code "39") (name "Net-(U6-IO0)") (class "Default")
      (node (ref "IO0") (pin "2") (pinfunction "2_2") (pintype "input"))
      (node (ref "R17") (pin "1") (pinfunction "1_1") (pintype "input"))
      (node (ref "U6") (pin "25") (pinfunction "IO0_25") (pintype "input"))
    )
    (net (code "40") (name "Net-(U6-IO2)") (class "Default")
      (node (ref "R16") (pin "2") (pinfunction "2_2") (pintype "input"))
      (node (ref "U6") (pin "24") (pinfunction "IO2_24") (pintype "input"))
    )
    (net (code "41") (name "Net-(U11-BOOT)") (class "Default")
      (node (ref "C22") (pin "2") (pinfunction "2_2") (pintype "input"))
      (node (ref "U11") (pin "1") (pinfunction "BOOT_1") (pintype "unspecified"))
    )
    (net (code "42") (name "VCC") (class "Default")
      (node (ref "C2") (pin "1") (pinfunction "1_1") (pintype "input"))
      (node (ref "C23") (pin "2") (pinfunction "2_2") (pintype "unspecified"))
      (node (ref "C4") (pin "2") (pinfunction "2_2") (pintype "input"))
      (node (ref "R14") (pin "1") (pinfunction "1_1") (pintype "input"))
      (node (ref "U1") (pin "11") (pinfunction "VM_11") (pintype "input"))
      (node (ref "U1") (pin "4") (pinfunction "VM_4") (pintype "input"))
      (node (ref "U11") (pin "7") (pinfunction "VIN_7") (pintype "unspecified"))
      (node (ref "VIN1") (pin "1") (pinfunction "1_1") (pintype "unspecified"))
      (node (ref "VIN2") (pin "1") (pinfunction "1_1") (pintype "unspecified"))
    )
    (net (code "43") (name "unconnected-(U1-FAULT#-Pad18)") (class "Default")
      (node (ref "U1") (pin "18") (pinfunction "FAULT#_18") (pintype "input+no_connect"))
    )
    (net (code "44") (name "unconnected-(U2-OUT-Pad3)") (class "Default")
      (node (ref "U2") (pin "3") (pinfunction "OUT_3") (pintype "input+no_connect"))
    )
    (net (code "45") (name "unconnected-(U6-CLK-Pad20)") (class "Default")
      (node (ref "U6") (pin "20") (pinfunction "CLK_20") (pintype "input+no_connect"))
    )
    (net (code "46") (name "unconnected-(U6-CMD-Pad19)") (class "Default")
      (node (ref "U6") (pin "19") (pinfunction "CMD_19") (pintype "input+no_connect"))
    )
    (net (code "47") (name "unconnected-(U6-IO4-Pad26)") (class "Default")
      (node (ref "U6") (pin "26") (pinfunction "IO4_26") (pintype "input+no_connect"))
    )
    (net (code "48") (name "unconnected-(U6-IO5-Pad29)") (class "Default")
      (node (ref "U6") (pin "29") (pinfunction "IO5_29") (pintype "input+no_connect"))
    )
    (net (code "49") (name "unconnected-(U6-IO12-Pad14)") (class "Default")
      (node (ref "U6") (pin "14") (pinfunction "IO12_14") (pintype "input+no_connect"))
    )
    (net (code "50") (name "unconnected-(U6-IO13-Pad16)") (class "Default")
      (node (ref "U6") (pin "16") (pinfunction "IO13_16") (pintype "input+no_connect"))
    )
    (net (code "51") (name "unconnected-(U6-IO15-Pad23)") (class "Default")
      (node (ref "U6") (pin "23") (pinfunction "IO15_23") (pintype "input+no_connect"))
    )
    (net (code "52") (name "unconnected-(U6-IO16-Pad27)") (class "Default")
      (node (ref "U6") (pin "27") (pinfunction "IO16_27") (pintype "input+no_connect"))
    )
    (net (code "53") (name "unconnected-(U6-IO17-Pad28)") (class "Default")
      (node (ref "U6") (pin "28") (pinfunction "IO17_28") (pintype "input+no_connect"))
    )
    (net (code "54") (name "unconnected-(U6-IO32-Pad8)") (class "Default")
      (node (ref "U6") (pin "8") (pinfunction "IO32_8") (pintype "input+no_connect"))
    )
    (net (code "55") (name "unconnected-(U6-IO33-Pad9)") (class "Default")
      (node (ref "U6") (pin "9") (pinfunction "IO33_9") (pintype "input+no_connect"))
    )
    (net (code "56") (name "unconnected-(U6-NC-Pad32)") (class "Default")
      (node (ref "U6") (pin "32") (pinfunction "NC_32") (pintype "input+no_connect"))
    )
    (net (code "57") (name "unconnected-(U6-SD2-Pad17)") (class "Default")
      (node (ref "U6") (pin "17") (pinfunction "SD2_17") (pintype "input+no_connect"))
    )
    (net (code "58") (name "unconnected-(U6-SD3-Pad18)") (class "Default")
      (node (ref "U6") (pin "18") (pinfunction "SD3_18") (pintype "input+no_connect"))
    )
    (net (code "59") (name "unconnected-(U6-SDI-Pad22)") (class "Default")
      (node (ref "U6") (pin "22") (pinfunction "SDI_22") (pintype "input+no_connect"))
    )
    (net (code "60") (name "unconnected-(U6-SDO-Pad21)") (class "Default")
      (node (ref "U6") (pin "21") (pinfunction "SDO_21") (pintype "input+no_connect"))
    )
    (net (code "61") (name "unconnected-(U9-S-Pad8)") (class "Default")
      (node (ref "U9") (pin "8") (pinfunction "S_8") (pintype "input+no_connect"))
    )
    (net (code "62") (name "unconnected-(U9-VIO-Pad5)") (class "Default")
      (node (ref "U9") (pin "5") (pinfunction "VIO_5") (pintype "input+no_connect"))
    )
    (net (code "63") (name "unconnected-(U11-ENA-Pad5)") (class "Default")
      (node (ref "U11") (pin "5") (pinfunction "ENA_5") (pintype "unspecified+no_connect"))
    )
    (net (code "64") (name "unconnected-(U11-NC-Pad2)") (class "Default")
      (node (ref "U11") (pin "2") (pinfunction "NC_2") (pintype "unspecified+no_connect"))
    )
    (net (code "65") (name "unconnected-(U11-NC-Pad3)") (class "Default")
      (node (ref "U11") (pin "3") (pinfunction "NC_3") (pintype "unspecified+no_connect"))
    )
  )
)
